# ESP32.net
KiCad netlist of a schematic drawn in Altium Designer
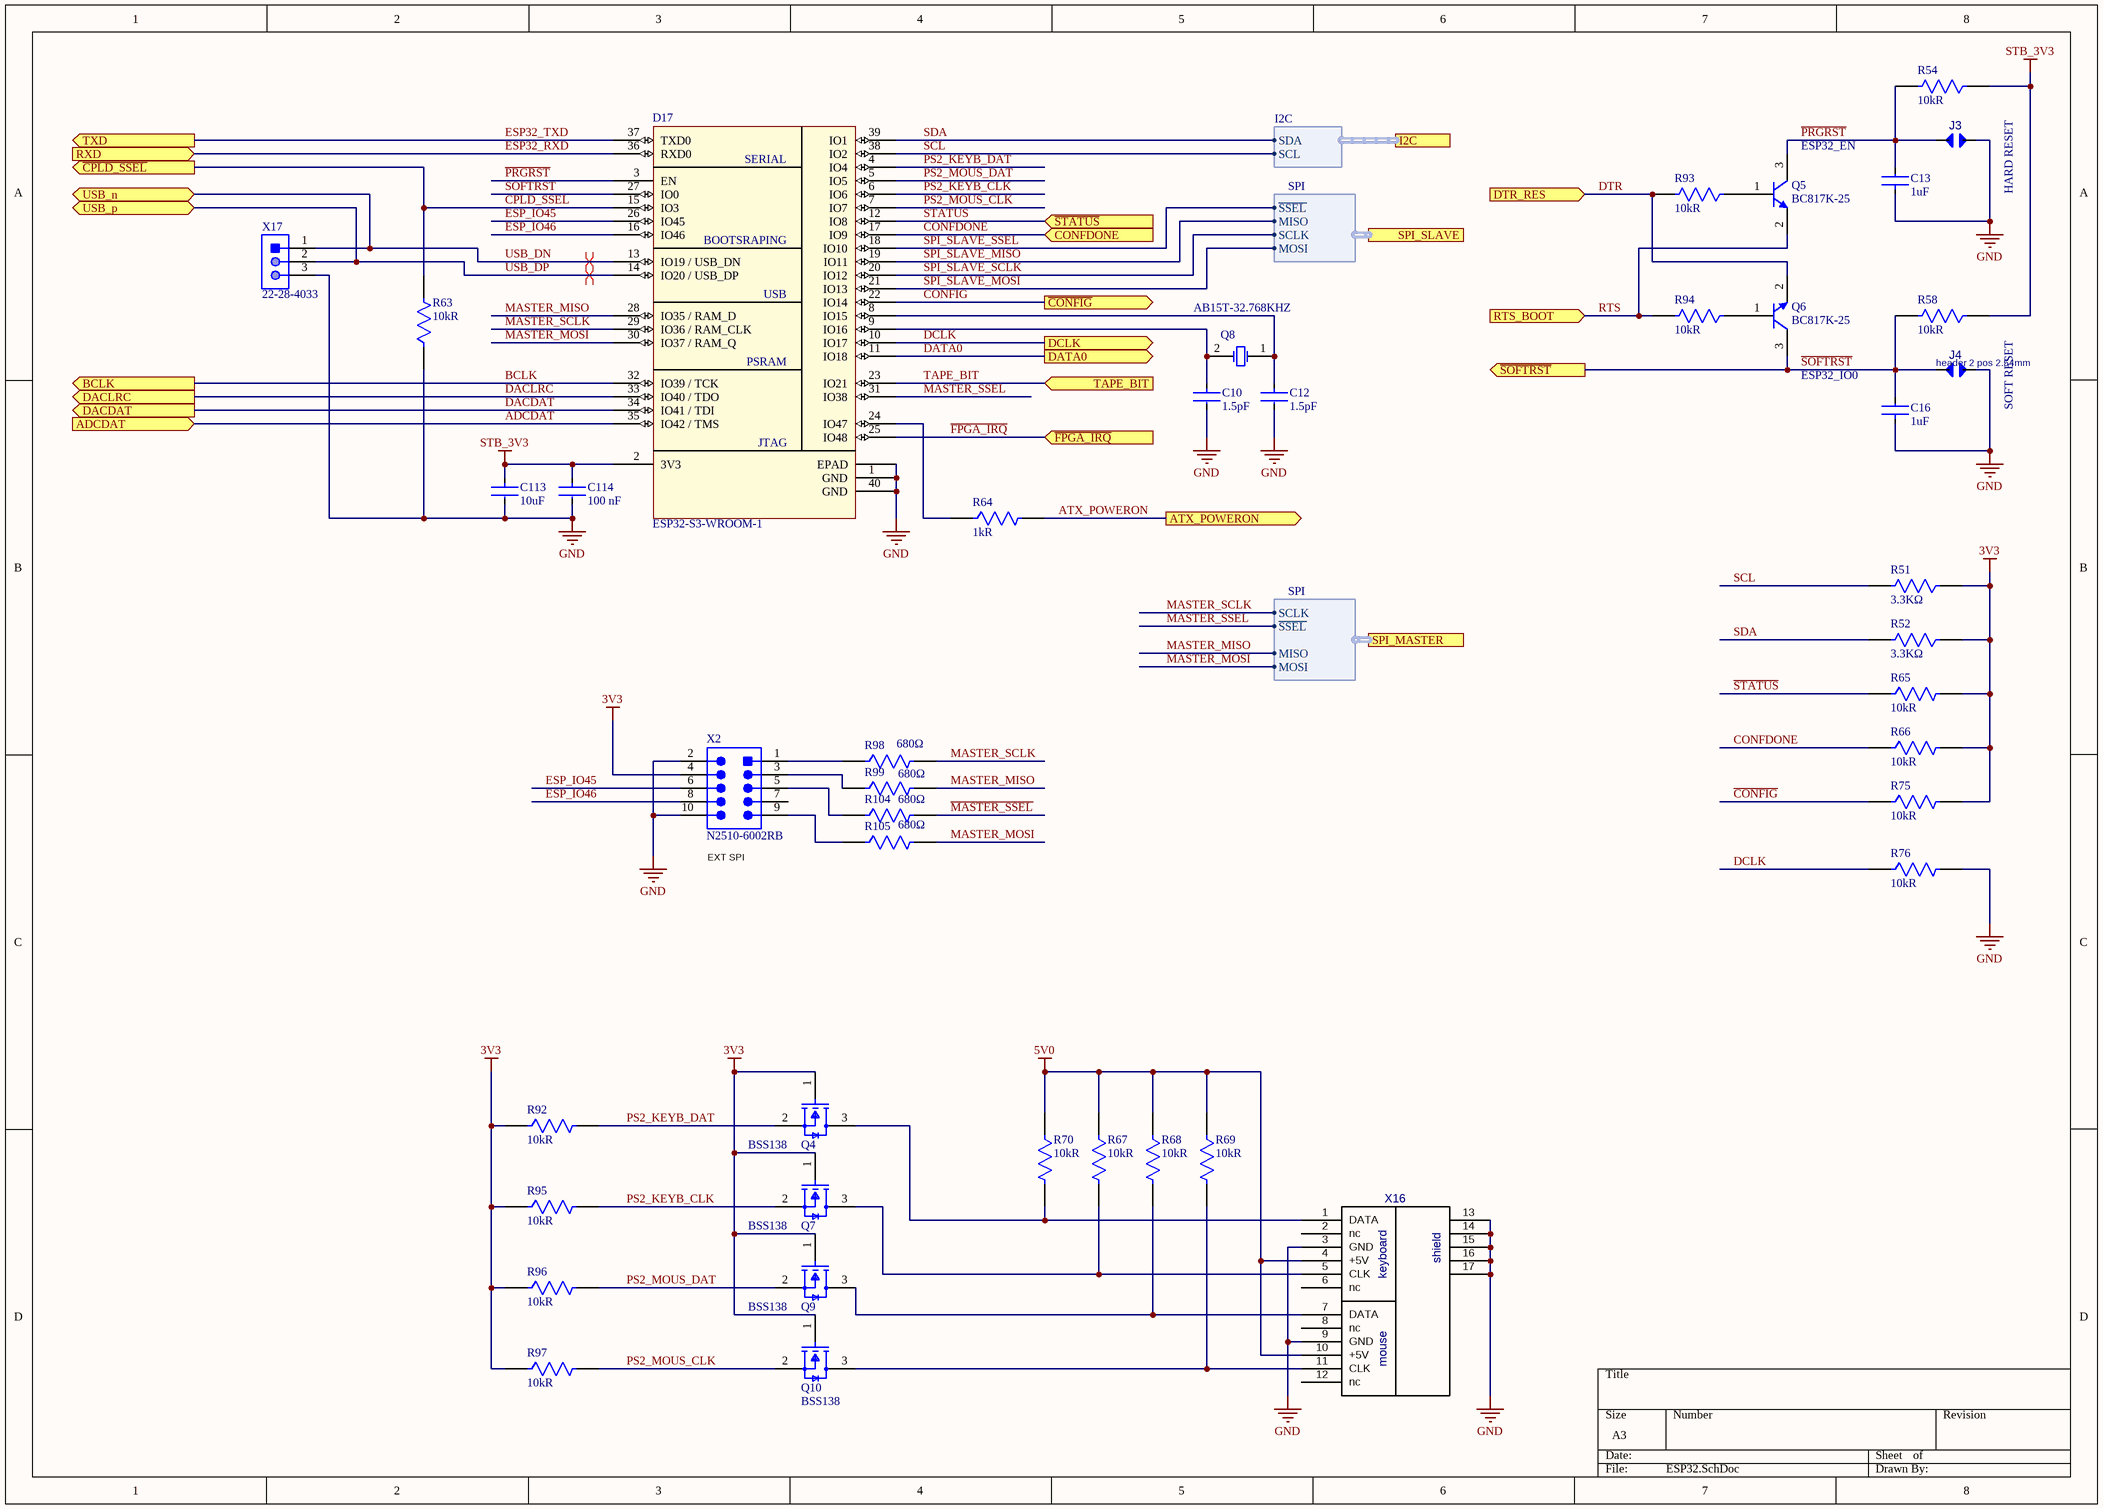
[diagram p0: ESP32.SchDoc]

(export (version "E")
  (design (tool "Eeschema 10.0.6"))
  (components
    (comp (ref "C10")
      (value "CL21C1R5CBANNNC")
      (footprint "FP-CL21-IPC_A")
      (description "CL21 Series 0805 1.5pF 50V ±0.25pF Tolerance C0G Multilayer Ceramic Chip Capacitor")
      (fields (field (name "CAPACITANCE") "1.5pF") (field (name "MANUFACTURER") "Samsung"))
      (libsource (lib "zxevo") (part "CMP-13271-001925-1"))
    )
    (comp (ref "C12")
      (value "CL21C1R5CBANNNC")
      (footprint "FP-CL21-IPC_A")
      (description "CL21 Series 0805 1.5pF 50V ±0.25pF Tolerance C0G Multilayer Ceramic Chip Capacitor")
      (fields (field (name "CAPACITANCE") "1.5pF") (field (name "MANUFACTURER") "Samsung"))
      (libsource (lib "zxevo") (part "CMP-13271-001925-1"))
    )
    (comp (ref "C13")
      (value "GCM21BR71E105KA56L")
      (footprint "FP-GCM21B-0_15-IPC_A")
      (description "Ceramic Capacitor for Automotive 1uF ±10% 25VDC X7R 0805 Embossed T/R")
      (fields (field (name "CAPACITANCE") "1uF") (field (name "MANUFACTURER") "Murata"))
      (libsource (lib "zxevo") (part "CMP-2007-03346-2"))
    )
    (comp (ref "C16")
      (value "GCM21BR71E105KA56L")
      (footprint "FP-GCM21B-0_15-IPC_A")
      (description "Ceramic Capacitor for Automotive 1uF ±10% 25VDC X7R 0805 Embossed T/R")
      (fields (field (name "CAPACITANCE") "1uF") (field (name "MANUFACTURER") "Murata"))
      (libsource (lib "zxevo") (part "CMP-2007-03346-2"))
    )
    (comp (ref "C113")
      (value "C0805C106K8PACTU")
      (footprint "FP-C0805C-DG-IPC_A")
      (description "CAP CER 10UF 10V X5R 0805")
      (fields (field (name "MANUFACTURER") "KEMET") (field (name "CAPACITANCE") "10uF"))
      (libsource (lib "zxevo") (part "CMP-2007-03243-2"))
    )
    (comp (ref "C114")
      (value "CC0805KRX7R9BB104")
      (footprint "FP-CC0805-0_85-IPC_A")
      (description "CAP CER 0.1UF 50V X7R 0805")
      (fields (field (name "MANUFACTURER") "Yageo") (field (name "CAPACITANCE") "100 nF"))
      (libsource (lib "zxevo") (part "CMP-2100-03606-3"))
    )
    (comp (ref "D17")
      (value "ESP32-S3-WROOM-1")
      (footprint "ESP32S3WROOM1")
      (libsource (lib "zxevo") (part "ESP32-S3-WROOM-1"))
    )
    (comp (ref "J3")
      (value "JUMPER")
      (footprint "JUMPER")
      (description "HLT->~IP")
      (libsource (lib "zxevo") (part "JUMPER"))
    )
    (comp (ref "J4")
      (value "header 2 pos 2.54mm")
      (footprint "JUMPER")
      (description "HLT->~IP")
      (fields (field (name "Comment") "JUMPER"))
      (libsource (lib "zxevo") (part "JUMPER"))
    )
    (comp (ref "Q4")
      (value "BSS138")
      (footprint "FP-318-08-IPC_B")
      (description "MOSFET N-CH 50V 220MA SOT-23")
      (fields (field (name "MANUFACTURER") "ON Semiconductor / Fairchild"))
      (libsource (lib "zxevo") (part "CMP-07173-000101-1"))
    )
    (comp (ref "Q5")
      (value "BC817K-25")
      (footprint "INF-SOT23_N")
      (description "NPN Silicon AF Transistor, 45 V VCEO, 500 mA IC, SOT23, Reel, Green")
      (fields (field (name "MANUFACTURER") "Infineon"))
      (libsource (lib "zxevo") (part "CMP-1177-00027-1"))
    )
    (comp (ref "Q6")
      (value "BC817K-25")
      (footprint "INF-SOT23_N")
      (description "NPN Silicon AF Transistor, 45 V VCEO, 500 mA IC, SOT23, Reel, Green")
      (fields (field (name "MANUFACTURER") "Infineon"))
      (libsource (lib "zxevo") (part "CMP-1177-00027-1"))
    )
    (comp (ref "Q7")
      (value "BSS138")
      (footprint "FP-318-08-IPC_B")
      (description "MOSFET N-CH 50V 220MA SOT-23")
      (fields (field (name "MANUFACTURER") "ON Semiconductor / Fairchild"))
      (libsource (lib "zxevo") (part "CMP-07173-000101-1"))
    )
    (comp (ref "Q8")
      (value "AB15T-32.768KHZ")
      (footprint "ABRA-AB15T-2_V")
      (fields (field (name "MANUFACTURER") "Abracon"))
      (libsource (lib "zxevo") (part "CMP-1326-00001-1"))
    )
    (comp (ref "Q9")
      (value "BSS138")
      (footprint "FP-318-08-IPC_B")
      (description "MOSFET N-CH 50V 220MA SOT-23")
      (fields (field (name "MANUFACTURER") "ON Semiconductor / Fairchild"))
      (libsource (lib "zxevo") (part "CMP-07173-000101-1"))
    )
    (comp (ref "Q10")
      (value "BSS138")
      (footprint "FP-318-08-IPC_B")
      (description "MOSFET N-CH 50V 220MA SOT-23")
      (fields (field (name "MANUFACTURER") "ON Semiconductor / Fairchild"))
      (libsource (lib "zxevo") (part "CMP-07173-000101-1"))
    )
    (comp (ref "R51")
      (value "RT0805FRE073K3L")
      (footprint "FP-RT0805-IPC_A")
      (description "RES SMD 3.3K OHM 1% 1/8W 0805")
      (fields (field (name "MANUFACTURER") "Yageo") (field (name "RESISTANCE") "3.3KΩ"))
      (libsource (lib "zxevo") (part "CMP-03412-025935-1"))
    )
    (comp (ref "R52")
      (value "RT0805FRE073K3L")
      (footprint "FP-RT0805-IPC_A")
      (description "RES SMD 3.3K OHM 1% 1/8W 0805")
      (fields (field (name "MANUFACTURER") "Yageo") (field (name "RESISTANCE") "3.3KΩ"))
      (libsource (lib "zxevo") (part "CMP-03412-025935-1"))
    )
    (comp (ref "R54")
      (value "CR0805-JW-103ELF")
      (footprint "FP-CR0805-IPC_A")
      (description "Thick Film Chip Resistors 0805 10kΩ 0.125W 5% 200ppm/°C")
      (fields (field (name "RESISTANCE") "10kR") (field (name "MANUFACTURER") "Bourns"))
      (libsource (lib "zxevo") (part "CMP-07231-003873-1"))
    )
    (comp (ref "R58")
      (value "CR0805-JW-103ELF")
      (footprint "FP-CR0805-IPC_A")
      (description "Thick Film Chip Resistors 0805 10kΩ 0.125W 5% 200ppm/°C")
      (fields (field (name "RESISTANCE") "10kR") (field (name "MANUFACTURER") "Bourns"))
      (libsource (lib "zxevo") (part "CMP-07231-003873-1"))
    )
    (comp (ref "R63")
      (value "CR0805-JW-103ELF")
      (footprint "FP-CR0805-IPC_A")
      (description "Thick Film Chip Resistors 0805 10kΩ 0.125W 5% 200ppm/°C")
      (fields (field (name "RESISTANCE") "10kR") (field (name "MANUFACTURER") "Bourns"))
      (libsource (lib "zxevo") (part "CMP-07231-003873-1"))
    )
    (comp (ref "R64")
      (value "MCR10ERTJ102")
      (footprint "FP-MCR10-IPC_A")
      (description "Thick Film Chip Resistor, 0805, 1kΩ, 5%, 200ppm/°C, 0.125W, 150V")
      (fields (field (name "RESISTANCE") "1kR") (field (name "MANUFACTURER") "Rohm"))
      (libsource (lib "zxevo") (part "CMP-08839-004390-1"))
    )
    (comp (ref "R65")
      (value "CR0805-JW-103ELF")
      (footprint "FP-CR0805-IPC_A")
      (description "Thick Film Chip Resistors 0805 10kΩ 0.125W 5% 200ppm/°C")
      (fields (field (name "RESISTANCE") "10kR") (field (name "MANUFACTURER") "Bourns"))
      (libsource (lib "zxevo") (part "CMP-07231-003873-1"))
    )
    (comp (ref "R66")
      (value "CR0805-JW-103ELF")
      (footprint "FP-CR0805-IPC_A")
      (description "Thick Film Chip Resistors 0805 10kΩ 0.125W 5% 200ppm/°C")
      (fields (field (name "RESISTANCE") "10kR") (field (name "MANUFACTURER") "Bourns"))
      (libsource (lib "zxevo") (part "CMP-07231-003873-1"))
    )
    (comp (ref "R67")
      (value "CR0805-JW-103ELF")
      (footprint "FP-CR0805-IPC_A")
      (description "Thick Film Chip Resistors 0805 10kΩ 0.125W 5% 200ppm/°C")
      (fields (field (name "RESISTANCE") "10kR") (field (name "MANUFACTURER") "Bourns"))
      (libsource (lib "zxevo") (part "CMP-07231-003873-1"))
    )
    (comp (ref "R68")
      (value "CR0805-JW-103ELF")
      (footprint "FP-CR0805-IPC_A")
      (description "Thick Film Chip Resistors 0805 10kΩ 0.125W 5% 200ppm/°C")
      (fields (field (name "RESISTANCE") "10kR") (field (name "MANUFACTURER") "Bourns"))
      (libsource (lib "zxevo") (part "CMP-07231-003873-1"))
    )
    (comp (ref "R69")
      (value "CR0805-JW-103ELF")
      (footprint "FP-CR0805-IPC_A")
      (description "Thick Film Chip Resistors 0805 10kΩ 0.125W 5% 200ppm/°C")
      (fields (field (name "RESISTANCE") "10kR") (field (name "MANUFACTURER") "Bourns"))
      (libsource (lib "zxevo") (part "CMP-07231-003873-1"))
    )
    (comp (ref "R70")
      (value "CR0805-JW-103ELF")
      (footprint "FP-CR0805-IPC_A")
      (description "Thick Film Chip Resistors 0805 10kΩ 0.125W 5% 200ppm/°C")
      (fields (field (name "RESISTANCE") "10kR") (field (name "MANUFACTURER") "Bourns"))
      (libsource (lib "zxevo") (part "CMP-07231-003873-1"))
    )
    (comp (ref "R75")
      (value "CR0805-JW-103ELF")
      (footprint "FP-CR0805-IPC_A")
      (description "Thick Film Chip Resistors 0805 10kΩ 0.125W 5% 200ppm/°C")
      (fields (field (name "RESISTANCE") "10kR") (field (name "MANUFACTURER") "Bourns"))
      (libsource (lib "zxevo") (part "CMP-07231-003873-1"))
    )
    (comp (ref "R76")
      (value "CR0805-JW-103ELF")
      (footprint "FP-CR0805-IPC_A")
      (description "Thick Film Chip Resistors 0805 10kΩ 0.125W 5% 200ppm/°C")
      (fields (field (name "RESISTANCE") "10kR") (field (name "MANUFACTURER") "Bourns"))
      (libsource (lib "zxevo") (part "CMP-07231-003873-1"))
    )
    (comp (ref "R92")
      (value "CR0805-JW-103ELF")
      (footprint "FP-CR0805-IPC_A")
      (description "Thick Film Chip Resistors 0805 10kΩ 0.125W 5% 200ppm/°C")
      (fields (field (name "RESISTANCE") "10kR") (field (name "MANUFACTURER") "Bourns"))
      (libsource (lib "zxevo") (part "CMP-07231-003873-1"))
    )
    (comp (ref "R93")
      (value "CR0805-JW-103ELF")
      (footprint "FP-CR0805-IPC_A")
      (description "Thick Film Chip Resistors 0805 10kΩ 0.125W 5% 200ppm/°C")
      (fields (field (name "RESISTANCE") "10kR") (field (name "MANUFACTURER") "Bourns"))
      (libsource (lib "zxevo") (part "CMP-07231-003873-1"))
    )
    (comp (ref "R94")
      (value "CR0805-JW-103ELF")
      (footprint "FP-CR0805-IPC_A")
      (description "Thick Film Chip Resistors 0805 10kΩ 0.125W 5% 200ppm/°C")
      (fields (field (name "RESISTANCE") "10kR") (field (name "MANUFACTURER") "Bourns"))
      (libsource (lib "zxevo") (part "CMP-07231-003873-1"))
    )
    (comp (ref "R95")
      (value "CR0805-JW-103ELF")
      (footprint "FP-CR0805-IPC_A")
      (description "Thick Film Chip Resistors 0805 10kΩ 0.125W 5% 200ppm/°C")
      (fields (field (name "RESISTANCE") "10kR") (field (name "MANUFACTURER") "Bourns"))
      (libsource (lib "zxevo") (part "CMP-07231-003873-1"))
    )
    (comp (ref "R96")
      (value "CR0805-JW-103ELF")
      (footprint "FP-CR0805-IPC_A")
      (description "Thick Film Chip Resistors 0805 10kΩ 0.125W 5% 200ppm/°C")
      (fields (field (name "RESISTANCE") "10kR") (field (name "MANUFACTURER") "Bourns"))
      (libsource (lib "zxevo") (part "CMP-07231-003873-1"))
    )
    (comp (ref "R97")
      (value "CR0805-JW-103ELF")
      (footprint "FP-CR0805-IPC_A")
      (description "Thick Film Chip Resistors 0805 10kΩ 0.125W 5% 200ppm/°C")
      (fields (field (name "RESISTANCE") "10kR") (field (name "MANUFACTURER") "Bourns"))
      (libsource (lib "zxevo") (part "CMP-07231-003873-1"))
    )
    (comp (ref "R98")
      (value "680Ω")
      (footprint "FP-RT0805-IPC_A")
      (description "RES SMD 680 OHM 1% 1/8W 0805")
      (fields
        (field (name "MANUFACTURER") "Yageo")
        (field (name "MANUFACTURER PART NUMBER") "RT0805FRE07680RL")
      )
      (libsource (lib "zxevo") (part "CMP-03412-000082-1"))
    )
    (comp (ref "R99")
      (value "680Ω")
      (footprint "FP-RT0805-IPC_A")
      (description "RES SMD 680 OHM 1% 1/8W 0805")
      (fields
        (field (name "MANUFACTURER") "Yageo")
        (field (name "MANUFACTURER PART NUMBER") "RT0805FRE07680RL")
      )
      (libsource (lib "zxevo") (part "CMP-03412-000082-1"))
    )
    (comp (ref "R104")
      (value "680Ω")
      (footprint "FP-RT0805-IPC_A")
      (description "RES SMD 680 OHM 1% 1/8W 0805")
      (fields
        (field (name "MANUFACTURER") "Yageo")
        (field (name "MANUFACTURER PART NUMBER") "RT0805FRE07680RL")
      )
      (libsource (lib "zxevo") (part "CMP-03412-000082-1"))
    )
    (comp (ref "R105")
      (value "680Ω")
      (footprint "FP-RT0805-IPC_A")
      (description "RES SMD 680 OHM 1% 1/8W 0805")
      (fields
        (field (name "MANUFACTURER") "Yageo")
        (field (name "MANUFACTURER PART NUMBER") "RT0805FRE07680RL")
      )
      (libsource (lib "zxevo") (part "CMP-03412-000082-1"))
    )
    (comp (ref "X2")
      (value "N2510-6002RB")
      (footprint "3M-N2510-6002-10_V")
      (fields (field (name "PARTNUMBER") "N2510") (field (name "MANUFACTURER") "3M"))
      (libsource (lib "zxevo") (part "CMP-2000-06794-1"))
    )
    (comp (ref "X16")
      (value "KEYB-MOUSE")
      (footprint "MDD-6FR")
      (libsource (lib "zxevo") (part "KEYB-MOUSE"))
    )
    (comp (ref "X17")
      (value "22-28-4033")
      (footprint "MOLX-22-28-4033_V")
      (description "Male Header, Pitch 2.54 mm, 1 x 3 Position, Height 8.38 mm, Tail Length 3.18 mm, RoHS, Bulk")
      (fields (field (name "MANUFACTURER") "Molex"))
      (libsource (lib "zxevo") (part "CMP-1676-00001-5"))
    )
  )
  (nets
    (net (code "3") (name "/ADCDAT") (class "Default")
      (node (ref "D17") (pin "35") (pinfunction "IO42_/_TMS_35") (pintype "bidirectional"))
    )
    (net (code "4") (name "/ATX_POWERON") (class "Default")
      (node (ref "R64") (pin "2") (pinfunction "2_2") (pintype "passive"))
    )
    (net (code "5") (name "/BCLK") (class "Default")
      (node (ref "D17") (pin "32") (pinfunction "IO39_/_TCK_32") (pintype "bidirectional"))
    )
    (net (code "6") (name "/CONFDONE") (class "Default")
      (node (ref "D17") (pin "17") (pinfunction "IO9_17") (pintype "bidirectional"))
      (node (ref "R66") (pin "1") (pinfunction "1_1") (pintype "passive"))
    )
    (net (code "7") (name "/DACDAT") (class "Default")
      (node (ref "D17") (pin "34") (pinfunction "IO41_/_TDI_34") (pintype "bidirectional"))
    )
    (net (code "8") (name "/DACLRC") (class "Default")
      (node (ref "D17") (pin "33") (pinfunction "IO40_/_TDO_33") (pintype "bidirectional"))
    )
    (net (code "9") (name "/DATA0") (class "Default")
      (node (ref "D17") (pin "11") (pinfunction "IO18_11") (pintype "bidirectional"))
    )
    (net (code "10") (name "/DCLK") (class "Default")
      (node (ref "D17") (pin "10") (pinfunction "IO17_10") (pintype "bidirectional"))
      (node (ref "R76") (pin "1") (pinfunction "1_1") (pintype "passive"))
    )
    (net (code "11") (name "/DTR") (class "Default")
      (node (ref "Q6") (pin "2") (pinfunction "E_2") (pintype "passive"))
      (node (ref "R93") (pin "2") (pinfunction "2_2") (pintype "passive"))
    )
    (net (code "12") (name "/ESP32_RXD") (class "Default")
      (node (ref "D17") (pin "36") (pinfunction "RXD0_36") (pintype "bidirectional"))
    )
    (net (code "13") (name "/ESP32_TXD") (class "Default")
      (node (ref "D17") (pin "37") (pinfunction "TXD0_37") (pintype "bidirectional"))
    )
    (net (code "14") (name "/ESP_IO45") (class "Default")
      (node (ref "D17") (pin "26") (pinfunction "IO45_26") (pintype "bidirectional"))
      (node (ref "X2") (pin "6") (pinfunction "6_6") (pintype "passive"))
    )
    (net (code "15") (name "/ESP_IO46") (class "Default")
      (node (ref "D17") (pin "16") (pinfunction "IO46_16") (pintype "bidirectional"))
      (node (ref "X2") (pin "8") (pinfunction "8_8") (pintype "passive"))
    )
    (net (code "16") (name "/MASTER_MISO") (class "Default")
      (node (ref "D17") (pin "28") (pinfunction "IO35_/_RAM_D_28") (pintype "bidirectional"))
      (node (ref "R99") (pin "2") (pinfunction "2_2") (pintype "passive"))
    )
    (net (code "17") (name "/MASTER_MOSI") (class "Default")
      (node (ref "D17") (pin "30") (pinfunction "IO37_/_RAM_Q_30") (pintype "bidirectional"))
      (node (ref "R105") (pin "2") (pinfunction "2_2") (pintype "passive"))
    )
    (net (code "18") (name "/MASTER_SCLK") (class "Default")
      (node (ref "D17") (pin "29") (pinfunction "IO36_/_RAM_CLK_29") (pintype "bidirectional"))
      (node (ref "R98") (pin "2") (pinfunction "2_2") (pintype "passive"))
    )
    (net (code "19") (name "/PS2_KEYB_CLK") (class "Default")
      (node (ref "D17") (pin "6") (pinfunction "IO6_6") (pintype "bidirectional"))
      (node (ref "Q7") (pin "2") (pinfunction "S_2") (pintype "passive"))
      (node (ref "R95") (pin "2") (pinfunction "2_2") (pintype "passive"))
    )
    (net (code "20") (name "/PS2_KEYB_DAT") (class "Default")
      (node (ref "D17") (pin "4") (pinfunction "IO4_4") (pintype "bidirectional"))
      (node (ref "Q4") (pin "2") (pinfunction "S_2") (pintype "passive"))
      (node (ref "R92") (pin "2") (pinfunction "2_2") (pintype "passive"))
    )
    (net (code "21") (name "/PS2_MOUS_CLK") (class "Default")
      (node (ref "D17") (pin "7") (pinfunction "IO7_7") (pintype "bidirectional"))
      (node (ref "Q10") (pin "2") (pinfunction "S_2") (pintype "passive"))
      (node (ref "R97") (pin "2") (pinfunction "2_2") (pintype "passive"))
    )
    (net (code "22") (name "/PS2_MOUS_DAT") (class "Default")
      (node (ref "D17") (pin "5") (pinfunction "IO5_5") (pintype "bidirectional"))
      (node (ref "Q9") (pin "2") (pinfunction "S_2") (pintype "passive"))
      (node (ref "R96") (pin "2") (pinfunction "2_2") (pintype "passive"))
    )
    (net (code "23") (name "/RTS") (class "Default")
      (node (ref "Q5") (pin "2") (pinfunction "E_2") (pintype "passive"))
      (node (ref "R94") (pin "2") (pinfunction "2_2") (pintype "passive"))
    )
    (net (code "24") (name "/SCL") (class "Default")
      (node (ref "D17") (pin "38") (pinfunction "IO2_38") (pintype "bidirectional"))
      (node (ref "R51") (pin "2") (pinfunction "2_2") (pintype "passive"))
    )
    (net (code "25") (name "/SDA") (class "Default")
      (node (ref "D17") (pin "39") (pinfunction "IO1_39") (pintype "bidirectional"))
      (node (ref "R52") (pin "2") (pinfunction "2_2") (pintype "passive"))
    )
    (net (code "26") (name "/SPI_SLAVE_MISO") (class "Default")
      (node (ref "D17") (pin "19") (pinfunction "IO11_19") (pintype "bidirectional"))
    )
    (net (code "27") (name "/SPI_SLAVE_MOSI") (class "Default")
      (node (ref "D17") (pin "21") (pinfunction "IO13_21") (pintype "bidirectional"))
    )
    (net (code "28") (name "/SPI_SLAVE_SCLK") (class "Default")
      (node (ref "D17") (pin "20") (pinfunction "IO12_20") (pintype "bidirectional"))
    )
    (net (code "29") (name "/TAPE_BIT") (class "Default")
      (node (ref "D17") (pin "23") (pinfunction "IO21_23") (pintype "bidirectional"))
    )
    (net (code "30") (name "/USB_DN") (class "Default")
      (node (ref "D17") (pin "13") (pinfunction "IO19_/_USB_DN_13") (pintype "bidirectional"))
      (node (ref "X17") (pin "1") (pinfunction "1_1") (pintype "passive"))
    )
    (net (code "31") (name "/USB_DP") (class "Default")
      (node (ref "D17") (pin "14") (pinfunction "IO20_/_USB_DP_14") (pintype "bidirectional"))
      (node (ref "X17") (pin "2") (pinfunction "2_2") (pintype "passive"))
    )
    (net (code "34") (name "/~{CONFIG}") (class "Default")
      (node (ref "D17") (pin "22") (pinfunction "IO14_22") (pintype "bidirectional"))
      (node (ref "R75") (pin "1") (pinfunction "1_1") (pintype "passive"))
    )
    (net (code "35") (name "/~{CPLD_SSEL}") (class "Default")
      (node (ref "D17") (pin "15") (pinfunction "IO3_15") (pintype "bidirectional"))
      (node (ref "R63") (pin "2") (pinfunction "2_2") (pintype "passive"))
    )
    (net (code "36") (name "/~{FPGA_IRQ}") (class "Default")
      (node (ref "D17") (pin "25") (pinfunction "IO48_25") (pintype "bidirectional"))
    )
    (net (code "37") (name "/~{MASTER_SSEL}") (class "Default")
      (node (ref "D17") (pin "31") (pinfunction "IO38_31") (pintype "bidirectional"))
      (node (ref "R104") (pin "2") (pinfunction "2_2") (pintype "passive"))
    )
    (net (code "38") (name "/~{PRGRST}") (class "Default")
      (node (ref "C13") (pin "2") (pinfunction "2_2") (pintype "passive"))
      (node (ref "D17") (pin "3") (pinfunction "EN_3") (pintype "power_in"))
      (node (ref "J3") (pin "0") (pinfunction "1_0") (pintype "passive"))
      (node (ref "Q5") (pin "3") (pinfunction "C_3") (pintype "passive"))
      (node (ref "R54") (pin "2") (pinfunction "2_2") (pintype "passive"))
    )
    (net (code "39") (name "/~{SOFTRST}") (class "Default")
      (node (ref "C16") (pin "2") (pinfunction "2_2") (pintype "passive"))
      (node (ref "D17") (pin "27") (pinfunction "IO0_27") (pintype "bidirectional"))
      (node (ref "J4") (pin "0") (pinfunction "1_0") (pintype "passive"))
      (node (ref "Q6") (pin "3") (pinfunction "C_3") (pintype "passive"))
      (node (ref "R58") (pin "2") (pinfunction "2_2") (pintype "passive"))
    )
    (net (code "40") (name "/~{SPI_SLAVE_SSEL}") (class "Default")
      (node (ref "D17") (pin "18") (pinfunction "IO10_18") (pintype "bidirectional"))
    )
    (net (code "41") (name "/~{STATUS}") (class "Default")
      (node (ref "D17") (pin "12") (pinfunction "IO8_12") (pintype "bidirectional"))
      (node (ref "R65") (pin "1") (pinfunction "1_1") (pintype "passive"))
    )
    (net (code "42") (name "3V3") (class "Default")
      (node (ref "Q10") (pin "1") (pinfunction "G_1") (pintype "passive"))
      (node (ref "Q4") (pin "1") (pinfunction "G_1") (pintype "passive"))
      (node (ref "Q7") (pin "1") (pinfunction "G_1") (pintype "passive"))
      (node (ref "Q9") (pin "1") (pinfunction "G_1") (pintype "passive"))
      (node (ref "R51") (pin "1") (pinfunction "1_1") (pintype "passive"))
      (node (ref "R52") (pin "1") (pinfunction "1_1") (pintype "passive"))
      (node (ref "R65") (pin "2") (pinfunction "2_2") (pintype "passive"))
      (node (ref "R66") (pin "2") (pinfunction "2_2") (pintype "passive"))
      (node (ref "R75") (pin "2") (pinfunction "2_2") (pintype "passive"))
      (node (ref "R92") (pin "1") (pinfunction "1_1") (pintype "passive"))
      (node (ref "R95") (pin "1") (pinfunction "1_1") (pintype "passive"))
      (node (ref "R96") (pin "1") (pinfunction "1_1") (pintype "passive"))
      (node (ref "R97") (pin "1") (pinfunction "1_1") (pintype "passive"))
      (node (ref "X2") (pin "4") (pinfunction "4_4") (pintype "passive"))
    )
    (net (code "43") (name "5V0") (class "Default")
      (node (ref "R67") (pin "1") (pinfunction "1_1") (pintype "passive"))
      (node (ref "R68") (pin "1") (pinfunction "1_1") (pintype "passive"))
      (node (ref "R69") (pin "1") (pinfunction "1_1") (pintype "passive"))
      (node (ref "R70") (pin "1") (pinfunction "1_1") (pintype "passive"))
      (node (ref "X16") (pin "10") (pinfunction "+5V_10") (pintype "passive"))
      (node (ref "X16") (pin "4") (pinfunction "+5V_4") (pintype "passive"))
    )
    (net (code "44") (name "GND") (class "Default")
      (node (ref "C10") (pin "2") (pinfunction "2_2") (pintype "passive"))
      (node (ref "C113") (pin "2") (pinfunction "2_2") (pintype "passive"))
      (node (ref "C114") (pin "2") (pinfunction "2_2") (pintype "passive"))
      (node (ref "C12") (pin "2") (pinfunction "2_2") (pintype "passive"))
      (node (ref "C13") (pin "1") (pinfunction "1_1") (pintype "passive"))
      (node (ref "C16") (pin "1") (pinfunction "1_1") (pintype "passive"))
      (node (ref "D17") (pin "1") (pinfunction "GND_1") (pintype "power_in"))
      (node (ref "D17") (pin "40") (pinfunction "GND_40") (pintype "power_in"))
      (node (ref "D17") (pin "EPAD") (pinfunction "EPAD_EPAD") (pintype "power_in"))
      (node (ref "J3") (pin "1") (pinfunction "2_1") (pintype "passive"))
      (node (ref "J4") (pin "1") (pinfunction "2_1") (pintype "passive"))
      (node (ref "R63") (pin "1") (pinfunction "1_1") (pintype "passive"))
      (node (ref "R76") (pin "2") (pinfunction "2_2") (pintype "passive"))
      (node (ref "X16") (pin "13") (pinfunction "shield_13") (pintype "passive"))
      (node (ref "X16") (pin "14") (pinfunction "shield_14") (pintype "passive"))
      (node (ref "X16") (pin "15") (pinfunction "shield_15") (pintype "passive"))
      (node (ref "X16") (pin "16") (pinfunction "shield_16") (pintype "passive"))
      (node (ref "X16") (pin "17") (pinfunction "shield_17") (pintype "passive"))
      (node (ref "X16") (pin "3") (pinfunction "GND_3") (pintype "passive"))
      (node (ref "X16") (pin "9") (pinfunction "GND_9") (pintype "passive"))
      (node (ref "X17") (pin "3") (pinfunction "3_3") (pintype "passive"))
      (node (ref "X2") (pin "10") (pinfunction "10_10") (pintype "passive"))
      (node (ref "X2") (pin "2") (pinfunction "2_2") (pintype "passive"))
    )
    (net (code "45") (name "Net-(D17-IO15)") (class "Default")
      (node (ref "C12") (pin "1") (pinfunction "1_1") (pintype "passive"))
      (node (ref "D17") (pin "8") (pinfunction "IO15_8") (pintype "bidirectional"))
      (node (ref "Q8") (pin "1") (pinfunction "X1_1") (pintype "passive"))
    )
    (net (code "46") (name "Net-(D17-IO16)") (class "Default")
      (node (ref "C10") (pin "1") (pinfunction "1_1") (pintype "passive"))
      (node (ref "D17") (pin "9") (pinfunction "IO16_9") (pintype "bidirectional"))
      (node (ref "Q8") (pin "2") (pinfunction "X2_2") (pintype "passive"))
    )
    (net (code "47") (name "Net-(D17-IO47)") (class "Default")
      (node (ref "D17") (pin "24") (pinfunction "IO47_24") (pintype "bidirectional"))
      (node (ref "R64") (pin "1") (pinfunction "1_1") (pintype "passive"))
    )
    (net (code "48") (name "Net-(Q4-D)") (class "Default")
      (node (ref "Q4") (pin "3") (pinfunction "D_3") (pintype "passive"))
      (node (ref "R70") (pin "2") (pinfunction "2_2") (pintype "passive"))
      (node (ref "X16") (pin "1") (pinfunction "DATA_1") (pintype "passive"))
    )
    (net (code "49") (name "Net-(Q5-B)") (class "Default")
      (node (ref "Q5") (pin "1") (pinfunction "B_1") (pintype "passive"))
      (node (ref "R93") (pin "1") (pinfunction "1_1") (pintype "passive"))
    )
    (net (code "50") (name "Net-(Q6-B)") (class "Default")
      (node (ref "Q6") (pin "1") (pinfunction "B_1") (pintype "passive"))
      (node (ref "R94") (pin "1") (pinfunction "1_1") (pintype "passive"))
    )
    (net (code "51") (name "Net-(Q7-D)") (class "Default")
      (node (ref "Q7") (pin "3") (pinfunction "D_3") (pintype "passive"))
      (node (ref "R67") (pin "2") (pinfunction "2_2") (pintype "passive"))
      (node (ref "X16") (pin "5") (pinfunction "CLK_5") (pintype "passive"))
    )
    (net (code "52") (name "Net-(Q9-D)") (class "Default")
      (node (ref "Q9") (pin "3") (pinfunction "D_3") (pintype "passive"))
      (node (ref "R68") (pin "2") (pinfunction "2_2") (pintype "passive"))
      (node (ref "X16") (pin "7") (pinfunction "DATA_7") (pintype "passive"))
    )
    (net (code "53") (name "Net-(Q10-D)") (class "Default")
      (node (ref "Q10") (pin "3") (pinfunction "D_3") (pintype "passive"))
      (node (ref "R69") (pin "2") (pinfunction "2_2") (pintype "passive"))
      (node (ref "X16") (pin "11") (pinfunction "CLK_11") (pintype "passive"))
    )
    (net (code "54") (name "Net-(R98-Pad1)") (class "Default")
      (node (ref "R98") (pin "1") (pinfunction "1_1") (pintype "passive"))
      (node (ref "X2") (pin "1") (pinfunction "1_1") (pintype "passive"))
    )
    (net (code "55") (name "Net-(R99-Pad1)") (class "Default")
      (node (ref "R99") (pin "1") (pinfunction "1_1") (pintype "passive"))
      (node (ref "X2") (pin "3") (pinfunction "3_3") (pintype "passive"))
    )
    (net (code "56") (name "Net-(R104-Pad1)") (class "Default")
      (node (ref "R104") (pin "1") (pinfunction "1_1") (pintype "passive"))
      (node (ref "X2") (pin "5") (pinfunction "5_5") (pintype "passive"))
    )
    (net (code "57") (name "Net-(R105-Pad1)") (class "Default")
      (node (ref "R105") (pin "1") (pinfunction "1_1") (pintype "passive"))
      (node (ref "X2") (pin "9") (pinfunction "9_9") (pintype "passive"))
    )
    (net (code "58") (name "STB_3V3") (class "Default")
      (node (ref "C113") (pin "1") (pinfunction "1_1") (pintype "passive"))
      (node (ref "C114") (pin "1") (pinfunction "1_1") (pintype "passive"))
      (node (ref "D17") (pin "2") (pinfunction "3V3_2") (pintype "power_in"))
      (node (ref "R54") (pin "1") (pinfunction "1_1") (pintype "passive"))
      (node (ref "R58") (pin "1") (pinfunction "1_1") (pintype "passive"))
    )
    (net (code "59") (name "unconnected-(X2-Pad7)") (class "Default")
      (node (ref "X2") (pin "7") (pinfunction "7_7") (pintype "passive"))
    )
    (net (code "60") (name "unconnected-(X16-nc-Pad2)") (class "Default")
      (node (ref "X16") (pin "2") (pinfunction "nc_2") (pintype "passive"))
    )
    (net (code "61") (name "unconnected-(X16-nc-Pad6)") (class "Default")
      (node (ref "X16") (pin "6") (pinfunction "nc_6") (pintype "passive"))
    )
    (net (code "62") (name "unconnected-(X16-nc-Pad8)") (class "Default")
      (node (ref "X16") (pin "8") (pinfunction "nc_8") (pintype "passive"))
    )
    (net (code "63") (name "unconnected-(X16-nc-Pad12)") (class "Default")
      (node (ref "X16") (pin "12") (pinfunction "nc_12") (pintype "passive"))
    )
  )
)
